# design1.net
KiCad netlist of a schematic drawn in EAGLE
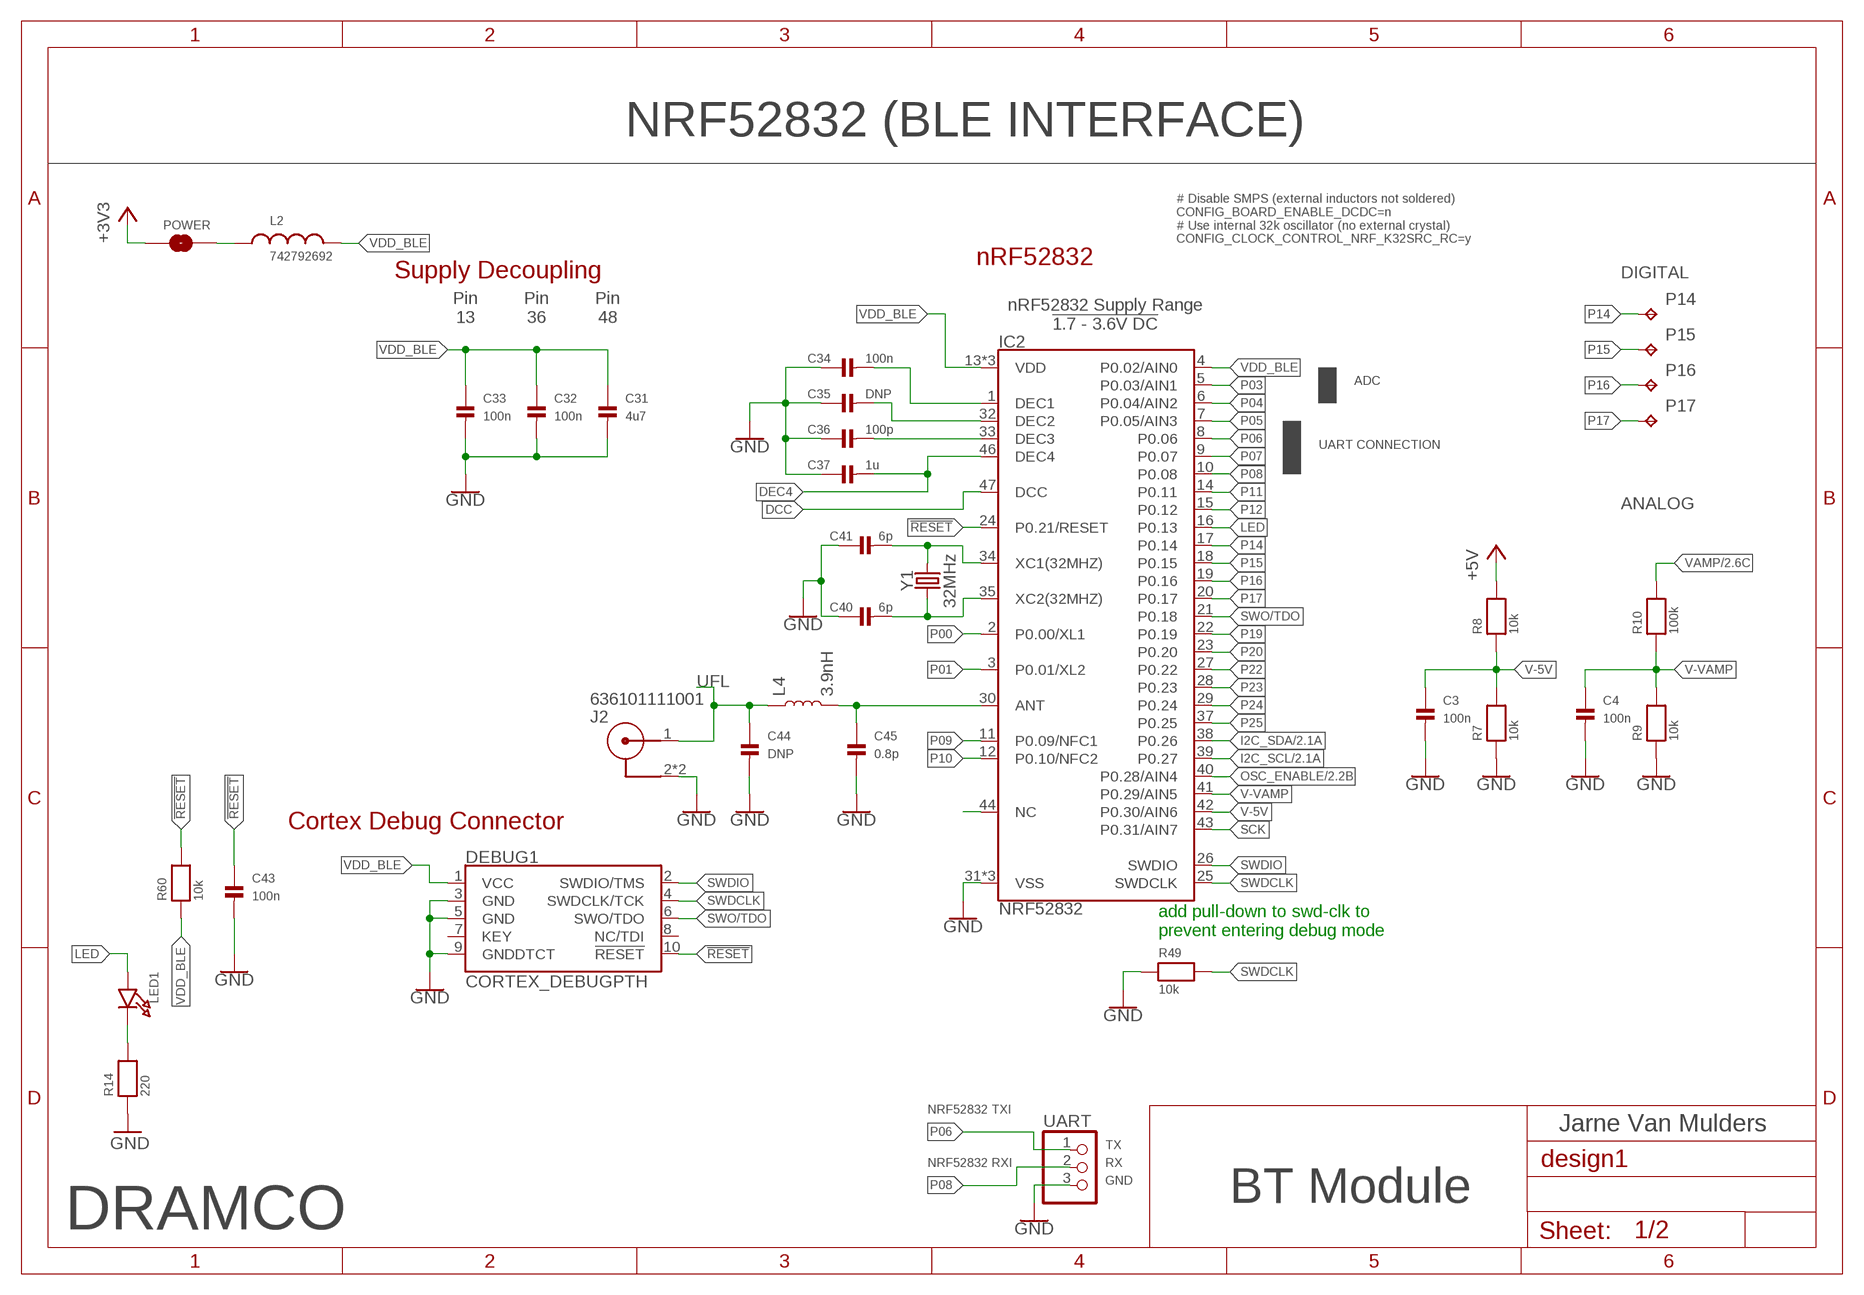
[diagram p0: schematic, sheet 1]
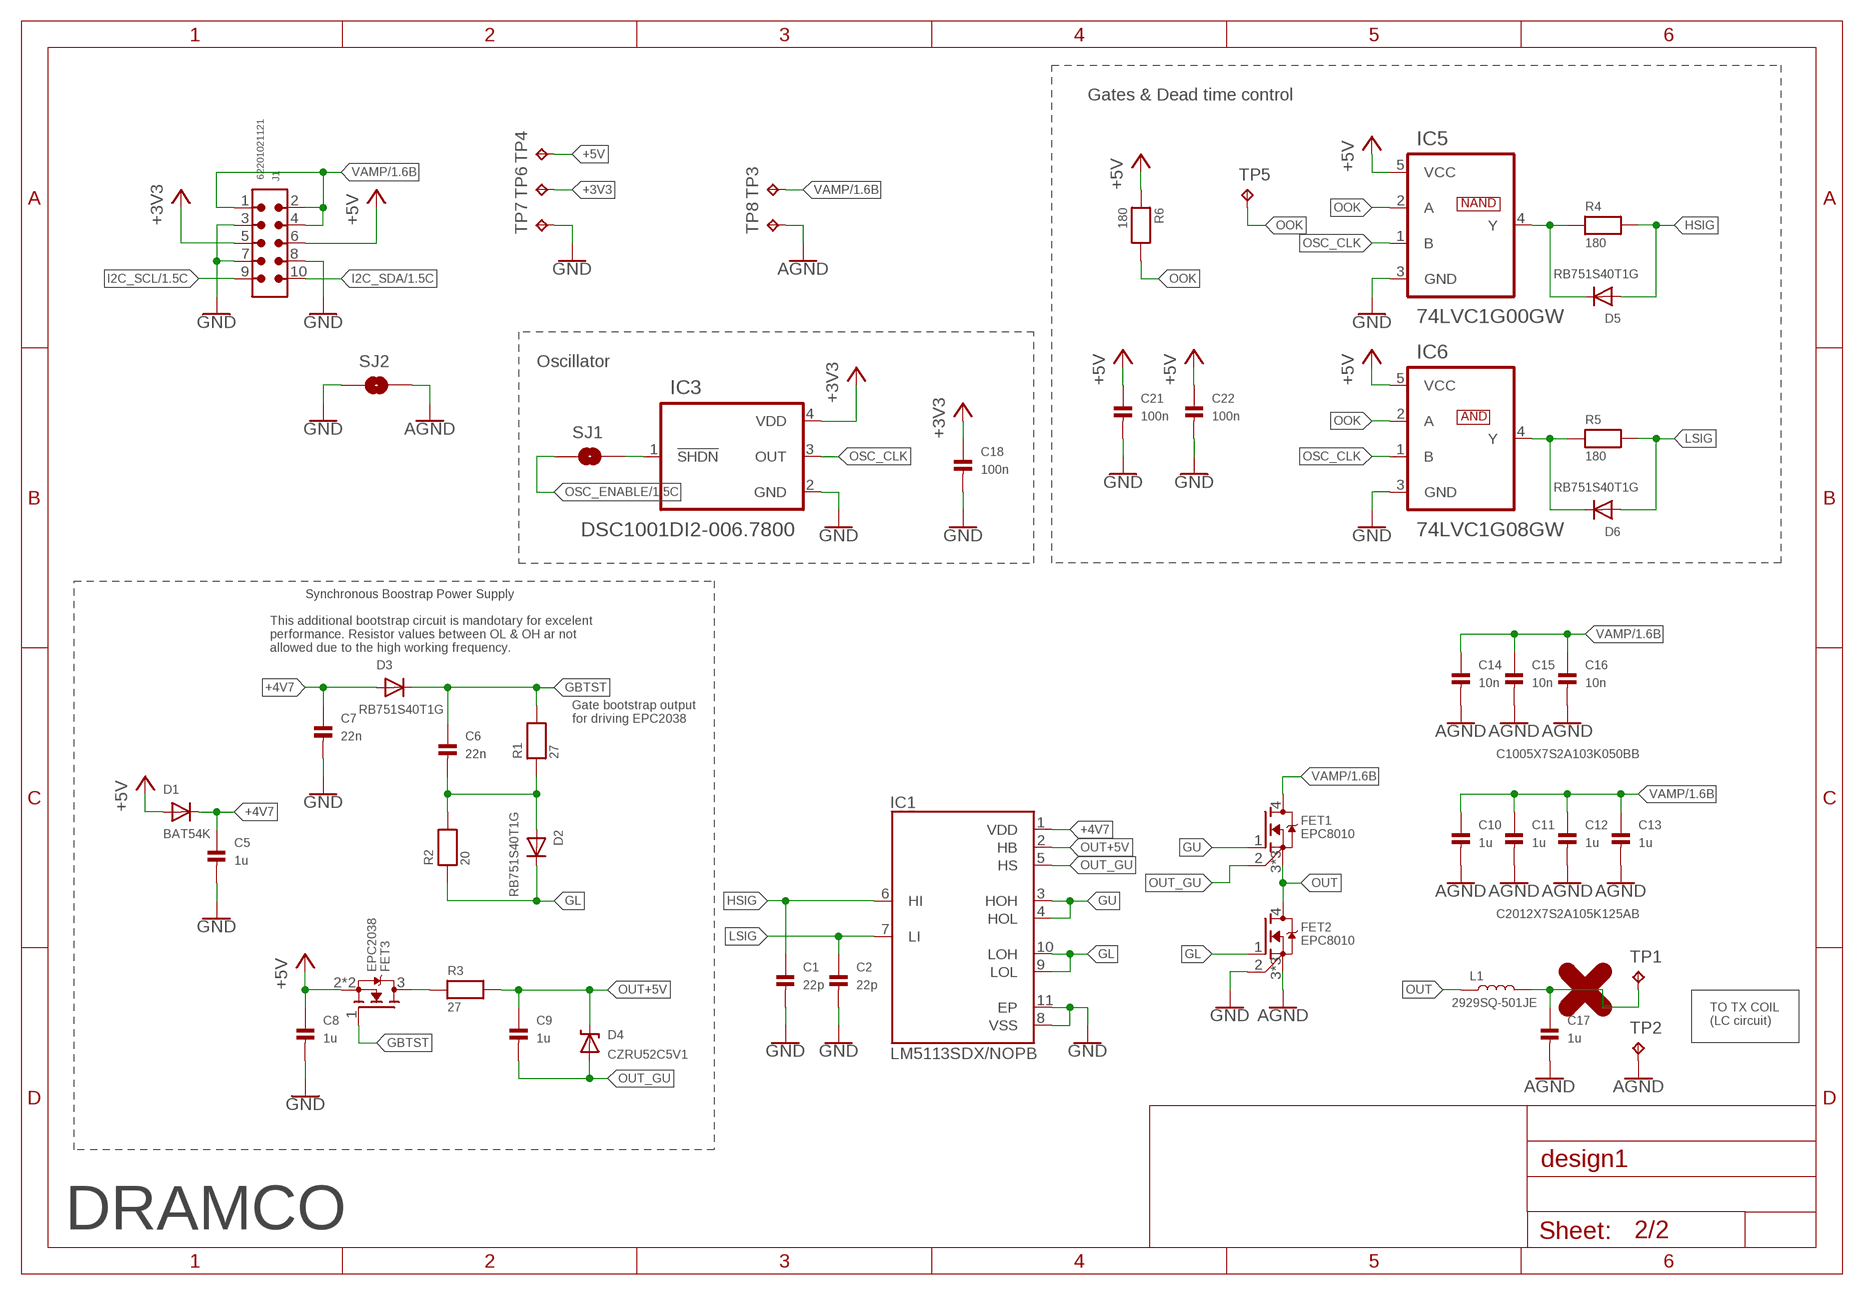
[diagram p1: schematic, sheet 2]

(export (version "E")
  (design (tool "Eeschema 10.0.6"))
  (components
    (comp (ref "C1")
      (value "22p")
      (footprint "eagle-import:0402")
      (libsource (lib "eagle-import") (part "CAP_CERAMIC0402"))
    )
    (comp (ref "C2")
      (value "22p")
      (footprint "eagle-import:0402")
      (libsource (lib "eagle-import") (part "CAP_CERAMIC0402"))
    )
    (comp (ref "C5")
      (value "1u")
      (footprint "eagle-import:0402")
      (libsource (lib "eagle-import") (part "CAP_CERAMIC0402"))
    )
    (comp (ref "C6")
      (value "22n")
      (footprint "eagle-import:0402")
      (libsource (lib "eagle-import") (part "CAP_CERAMIC0402"))
    )
    (comp (ref "C7")
      (value "22n")
      (footprint "eagle-import:0402")
      (libsource (lib "eagle-import") (part "CAP_CERAMIC0402"))
    )
    (comp (ref "C8")
      (value "1u")
      (footprint "eagle-import:0402")
      (libsource (lib "eagle-import") (part "CAP_CERAMIC0402"))
    )
    (comp (ref "C9")
      (value "1u")
      (footprint "eagle-import:0402")
      (libsource (lib "eagle-import") (part "CAP_CERAMIC0402"))
    )
    (comp (ref "C10")
      (value "1u")
      (footprint "eagle-import:0805")
      (libsource (lib "eagle-import") (part "CAP_CERAMIC0805"))
    )
    (comp (ref "C11")
      (value "1u")
      (footprint "eagle-import:0805")
      (libsource (lib "eagle-import") (part "CAP_CERAMIC0805"))
    )
    (comp (ref "C12")
      (value "1u")
      (footprint "eagle-import:0805")
      (libsource (lib "eagle-import") (part "CAP_CERAMIC0805"))
    )
    (comp (ref "C13")
      (value "1u")
      (footprint "eagle-import:0805")
      (libsource (lib "eagle-import") (part "CAP_CERAMIC0805"))
    )
    (comp (ref "C14")
      (value "10n")
      (footprint "eagle-import:0402")
      (libsource (lib "eagle-import") (part "CAP_CERAMIC0402"))
    )
    (comp (ref "C15")
      (value "10n")
      (footprint "eagle-import:0402")
      (libsource (lib "eagle-import") (part "CAP_CERAMIC0402"))
    )
    (comp (ref "C16")
      (value "10n")
      (footprint "eagle-import:0402")
      (libsource (lib "eagle-import") (part "CAP_CERAMIC0402"))
    )
    (comp (ref "C17")
      (value "1u")
      (footprint "eagle-import:0805")
      (libsource (lib "eagle-import") (part "CAP_CERAMIC0805"))
    )
    (comp (ref "C18")
      (value "100n")
      (footprint "eagle-import:0603")
      (libsource (lib "eagle-import") (part "CAP_CERAMIC0603"))
    )
    (comp (ref "C21")
      (value "100n")
      (footprint "eagle-import:0402")
      (libsource (lib "eagle-import") (part "CAP_CERAMIC0402"))
    )
    (comp (ref "C22")
      (value "100n")
      (footprint "eagle-import:0402")
      (libsource (lib "eagle-import") (part "CAP_CERAMIC0402"))
    )
    (comp (ref "D1")
      (value "BAT54K")
      (footprint "eagle-import:SOD-523")
      (libsource (lib "eagle-import") (part "DIODESOD-523"))
    )
    (comp (ref "D2")
      (value "RB751S40T1G")
      (footprint "eagle-import:SOD-523")
      (libsource (lib "eagle-import") (part "DIODESOD-523"))
    )
    (comp (ref "D3")
      (value "RB751S40T1G")
      (footprint "eagle-import:SOD-523")
      (libsource (lib "eagle-import") (part "DIODESOD-523"))
    )
    (comp (ref "D4")
      (value "CZRU52C5V1")
      (footprint "eagle-import:SOD-523F")
      (libsource (lib "eagle-import") (part "CZRU52"))
    )
    (comp (ref "D5")
      (value "RB751S40T1G")
      (footprint "eagle-import:SOD-523")
      (libsource (lib "eagle-import") (part "DIODESOD-523"))
    )
    (comp (ref "D6")
      (value "RB751S40T1G")
      (footprint "eagle-import:SOD-523")
      (libsource (lib "eagle-import") (part "DIODESOD-523"))
    )
    (comp (ref "FET1")
      (value "EPC8010")
      (footprint "eagle-import:BGA-8010")
      (libsource (lib "eagle-import") (part "EPC8010"))
    )
    (comp (ref "FET2")
      (value "EPC8010")
      (footprint "eagle-import:BGA-8010")
      (libsource (lib "eagle-import") (part "EPC8010"))
    )
    (comp (ref "FET3")
      (value "EPC2038")
      (footprint "eagle-import:BGA-2038")
      (libsource (lib "eagle-import") (part "EPC2038"))
    )
    (comp (ref "IC1")
      (value "LM5113SDX/NOPB")
      (footprint "eagle-import:SON80P400X400X80-11N")
      (fields (field (name "MF") "Texas Instruments"))
      (libsource (lib "eagle-import") (part "LM5113SDX/NOPB"))
    )
    (comp (ref "IC3")
      (value "DSC1001DI2-006.7800")
      (footprint "eagle-import:2.5X2.0MMPLASTICPACKAGE")
      (fields (field (name "MF") "Microchip") (field (name "MP") "DSC1001DI1-025.0000"))
      (libsource (lib "eagle-import") (part "DSC1001DI2-006.7800"))
    )
    (comp (ref "IC5")
      (value "74LVC1G00GW")
      (footprint "eagle-import:SOT65P210X110-5N")
      (fields (field (name "MF") "Nexperia USA"))
      (libsource (lib "eagle-import") (part "74LVC1G00GW"))
    )
    (comp (ref "IC6")
      (value "74LVC1G08GW")
      (footprint "eagle-import:SOT65P210X110-5N")
      (fields (field (name "MF") "Nexperia USA") (field (name "MP") "74LVC1G00GW"))
      (libsource (lib "eagle-import") (part "74LVC1G00GW"))
    )
    (comp (ref "J1")
      (value "62201021121")
      (footprint "eagle-import:62201021121")
      (libsource (lib "eagle-import") (part "6220XX21121_62201021121"))
    )
    (comp (ref "L1")
      (value "2929SQ-501JE")
      (footprint "eagle-import:2929SQ-501")
      (libsource (lib "eagle-import") (part "2929SQ-501"))
    )
    (comp (ref "R1")
      (value "27")
      (footprint "eagle-import:0402")
      (libsource (lib "eagle-import") (part "RESISTOR0402"))
    )
    (comp (ref "R2")
      (value "20")
      (footprint "eagle-import:0402")
      (libsource (lib "eagle-import") (part "RESISTOR0402"))
    )
    (comp (ref "R3")
      (value "27")
      (footprint "eagle-import:0402")
      (libsource (lib "eagle-import") (part "RESISTOR0402"))
    )
    (comp (ref "R4")
      (value "180")
      (footprint "eagle-import:0402")
      (libsource (lib "eagle-import") (part "RESISTOR0402"))
    )
    (comp (ref "R5")
      (value "180")
      (footprint "eagle-import:0402")
      (libsource (lib "eagle-import") (part "RESISTOR0402"))
    )
    (comp (ref "R6")
      (value "180")
      (footprint "eagle-import:0402")
      (libsource (lib "eagle-import") (part "RESISTOR0402"))
    )
    (comp (ref "SJ1")
      (value "SOLDERJUMPERNO")
      (footprint "eagle-import:SJ_2S-NO")
      (libsource (lib "eagle-import") (part "SOLDERJUMPERNO"))
    )
    (comp (ref "SJ2")
      (value "SOLDERJUMPERNO")
      (footprint "eagle-import:SJ_2S-NO")
      (libsource (lib "eagle-import") (part "SOLDERJUMPERNO"))
    )
    (comp (ref "TP1")
      (value "TPTP20SQ")
      (footprint "eagle-import:TP20SQ")
      (libsource (lib "eagle-import") (part "TPTP20SQ"))
    )
    (comp (ref "TP2")
      (value "TPTP20SQ")
      (footprint "eagle-import:TP20SQ")
      (libsource (lib "eagle-import") (part "TPTP20SQ"))
    )
    (comp (ref "TP3")
      (value "TPTP20SQ")
      (footprint "eagle-import:TP20SQ")
      (libsource (lib "eagle-import") (part "TPTP20SQ"))
    )
    (comp (ref "TP4")
      (value "TPTP10SQ")
      (footprint "eagle-import:TP10SQ")
      (libsource (lib "eagle-import") (part "TPTP10SQ"))
    )
    (comp (ref "TP5")
      (value "TPTP10SQ")
      (footprint "eagle-import:TP10SQ")
      (libsource (lib "eagle-import") (part "TPTP10SQ"))
    )
    (comp (ref "TP6")
      (value "TPTP10SQ")
      (footprint "eagle-import:TP10SQ")
      (libsource (lib "eagle-import") (part "TPTP10SQ"))
    )
    (comp (ref "TP7")
      (value "TPTP10SQ")
      (footprint "eagle-import:TP10SQ")
      (libsource (lib "eagle-import") (part "TPTP10SQ"))
    )
    (comp (ref "TP8")
      (value "TPTP20SQ")
      (footprint "eagle-import:TP20SQ")
      (libsource (lib "eagle-import") (part "TPTP20SQ"))
    )
    (comp (ref "C3")
      (value "100n")
      (footprint "eagle-import:0402")
      (libsource (lib "eagle-import") (part "CAP_CERAMIC0402"))
    )
    (comp (ref "C4")
      (value "100n")
      (footprint "eagle-import:0402")
      (libsource (lib "eagle-import") (part "CAP_CERAMIC0402"))
    )
    (comp (ref "C31")
      (value "4u7")
      (footprint "eagle-import:0603")
      (libsource (lib "eagle-import") (part "CAP_CERAMIC0603"))
    )
    (comp (ref "C32")
      (value "100n")
      (footprint "eagle-import:0402")
      (libsource (lib "eagle-import") (part "CAP_CERAMIC0402"))
    )
    (comp (ref "C33")
      (value "100n")
      (footprint "eagle-import:0402")
      (libsource (lib "eagle-import") (part "CAP_CERAMIC0402"))
    )
    (comp (ref "C34")
      (value "100n")
      (footprint "eagle-import:0402")
      (libsource (lib "eagle-import") (part "CAP_CERAMIC0402"))
    )
    (comp (ref "C35")
      (value "DNP")
      (footprint "eagle-import:0402")
      (libsource (lib "eagle-import") (part "CAP_CERAMIC0402"))
    )
    (comp (ref "C36")
      (value "100p")
      (footprint "eagle-import:0402")
      (libsource (lib "eagle-import") (part "CAP_CERAMIC0402"))
    )
    (comp (ref "C37")
      (value "1u")
      (footprint "eagle-import:0402")
      (libsource (lib "eagle-import") (part "CAP_CERAMIC0402"))
    )
    (comp (ref "C40")
      (value "6p")
      (footprint "eagle-import:0402")
      (libsource (lib "eagle-import") (part "CAP_CERAMIC0402"))
    )
    (comp (ref "C41")
      (value "6p")
      (footprint "eagle-import:0402")
      (libsource (lib "eagle-import") (part "CAP_CERAMIC0402"))
    )
    (comp (ref "C43")
      (value "100n")
      (footprint "eagle-import:0402")
      (libsource (lib "eagle-import") (part "CAP_CERAMIC0402"))
    )
    (comp (ref "C44")
      (value "DNP")
      (footprint "eagle-import:0402")
      (libsource (lib "eagle-import") (part "CAP_CERAMIC0402"))
    )
    (comp (ref "C45")
      (value "0.8p")
      (footprint "eagle-import:0402")
      (libsource (lib "eagle-import") (part "CAP_CERAMIC0402"))
    )
    (comp (ref "DEBUG1")
      (value "CORTEX_DEBUGPTH")
      (footprint "eagle-import:2X5-PTH-1.27MM")
      (libsource (lib "eagle-import") (part "CORTEX_DEBUGPTH"))
    )
    (comp (ref "IC2")
      (value "NRF52832")
      (footprint "eagle-import:QFN48-6X6MM-EXTENDED")
      (libsource (lib "eagle-import") (part "NRF52832-EXTENDED"))
    )
    (comp (ref "J2")
      (value "636101111001")
      (footprint "eagle-import:636101111001")
      (libsource (lib "eagle-import") (part "636101111001"))
    )
    (comp (ref "L2")
      (value "742792692")
      (footprint "eagle-import:WE-CBF_0603(W=2.2)")
      (libsource (lib "eagle-import") (part "WE-CBF_0603_WB_HS_742792692"))
    )
    (comp (ref "L4")
      (value "3.9nH")
      (footprint "eagle-import:0402")
      (libsource (lib "eagle-import") (part "INDUCTOR-0402-3.9NH"))
    )
    (comp (ref "LED1")
      (value "LED0805")
      (footprint "eagle-import:CHIPLED_0805")
      (libsource (lib "eagle-import") (part "LED0805"))
    )
    (comp (ref "P14")
      (value "TPTP10SQ")
      (footprint "eagle-import:TP10SQ")
      (libsource (lib "eagle-import") (part "TPTP10SQ"))
    )
    (comp (ref "P15")
      (value "TPTP10SQ")
      (footprint "eagle-import:TP10SQ")
      (libsource (lib "eagle-import") (part "TPTP10SQ"))
    )
    (comp (ref "P16")
      (value "TPTP10SQ")
      (footprint "eagle-import:TP10SQ")
      (libsource (lib "eagle-import") (part "TPTP10SQ"))
    )
    (comp (ref "P17")
      (value "TPTP10SQ")
      (footprint "eagle-import:TP10SQ")
      (libsource (lib "eagle-import") (part "TPTP10SQ"))
    )
    (comp (ref "POWER")
      (value "JUMPER-SMT_2_NO_NO-SILK")
      (footprint "eagle-import:SMT-JUMPER_2_NO_NO-SILK")
      (libsource (lib "eagle-import") (part "JUMPER-SMT_2_NO_NO-SILK"))
    )
    (comp (ref "R7")
      (value "10k")
      (footprint "eagle-import:0402")
      (libsource (lib "eagle-import") (part "RESISTOR0402"))
    )
    (comp (ref "R8")
      (value "10k")
      (footprint "eagle-import:0402")
      (libsource (lib "eagle-import") (part "RESISTOR0402"))
    )
    (comp (ref "R9")
      (value "10k")
      (footprint "eagle-import:0402")
      (libsource (lib "eagle-import") (part "RESISTOR0402"))
    )
    (comp (ref "R10")
      (value "100k")
      (footprint "eagle-import:0402")
      (libsource (lib "eagle-import") (part "RESISTOR0402"))
    )
    (comp (ref "R14")
      (value "220")
      (footprint "eagle-import:0603")
      (libsource (lib "eagle-import") (part "RESISTOR0603"))
    )
    (comp (ref "R49")
      (value "10k")
      (footprint "eagle-import:0402")
      (libsource (lib "eagle-import") (part "RESISTOR0402"))
    )
    (comp (ref "R60")
      (value "10k")
      (footprint "eagle-import:0402")
      (libsource (lib "eagle-import") (part "RESISTOR0402"))
    )
    (comp (ref "UART")
      (value "HEADER-1X3ROUND")
      (footprint "eagle-import:1X03_ROUND")
      (libsource (lib "eagle-import") (part "HEADER-1X3ROUND"))
    )
    (comp (ref "Y1")
      (value "32MHz")
      (footprint "eagle-import:CRYSTAL-SMD-2.0X1.6MM")
      (libsource (lib "eagle-import") (part "CRYSTAL-32MHZ-SMD-2.0X1.6MM"))
    )
  )
  (nets
    (net (code "1") (name "+3V3") (class "Default")
      (node (ref "C18") (pin "1") (pinfunction "P$1_1") (pintype "passive"))
      (node (ref "IC3") (pin "4") (pinfunction "VDD_4") (pintype "power_in"))
      (node (ref "J1") (pin "5") (pinfunction "5_5") (pintype "passive"))
      (node (ref "POWER") (pin "1") (pinfunction "1_1") (pintype "passive"))
      (node (ref "TP6") (pin "TP") (pinfunction "TP_TP") (pintype "input"))
    )
    (net (code "2") (name "+4V7") (class "Default")
      (node (ref "C5") (pin "1") (pinfunction "P$1_1") (pintype "passive"))
      (node (ref "C7") (pin "1") (pinfunction "P$1_1") (pintype "passive"))
      (node (ref "D1") (pin "K") (pinfunction "C_K") (pintype "passive"))
      (node (ref "D3") (pin "A") (pinfunction "A_A") (pintype "passive"))
      (node (ref "IC1") (pin "1") (pinfunction "VDD_1") (pintype "power_in"))
    )
    (net (code "3") (name "+5V") (class "Default")
      (node (ref "C21") (pin "1") (pinfunction "P$1_1") (pintype "passive"))
      (node (ref "C22") (pin "1") (pinfunction "P$1_1") (pintype "passive"))
      (node (ref "C8") (pin "1") (pinfunction "P$1_1") (pintype "passive"))
      (node (ref "D1") (pin "A") (pinfunction "A_A") (pintype "passive"))
      (node (ref "FET3") (pin "2") (pinfunction "S_2") (pintype "bidirectional"))
      (node (ref "FET3") (pin "4") (pinfunction "S_4") (pintype "bidirectional"))
      (node (ref "IC5") (pin "5") (pinfunction "VCC_5") (pintype "power_in"))
      (node (ref "IC6") (pin "5") (pinfunction "VCC_5") (pintype "power_in"))
      (node (ref "J1") (pin "6") (pinfunction "6_6") (pintype "passive"))
      (node (ref "R6") (pin "1") (pinfunction "1_1") (pintype "passive"))
      (node (ref "R8") (pin "2") (pinfunction "2_2") (pintype "passive"))
      (node (ref "TP4") (pin "TP") (pinfunction "TP_TP") (pintype "input"))
    )
    (net (code "4") (name "AGND") (class "Default")
      (node (ref "C10") (pin "2") (pinfunction "P$2_2") (pintype "passive"))
      (node (ref "C11") (pin "2") (pinfunction "P$2_2") (pintype "passive"))
      (node (ref "C12") (pin "2") (pinfunction "P$2_2") (pintype "passive"))
      (node (ref "C13") (pin "2") (pinfunction "P$2_2") (pintype "passive"))
      (node (ref "C14") (pin "2") (pinfunction "P$2_2") (pintype "passive"))
      (node (ref "C15") (pin "2") (pinfunction "P$2_2") (pintype "passive"))
      (node (ref "C16") (pin "2") (pinfunction "P$2_2") (pintype "passive"))
      (node (ref "C17") (pin "2") (pinfunction "P$2_2") (pintype "passive"))
      (node (ref "FET2") (pin "3") (pinfunction "S_3") (pintype "bidirectional"))
      (node (ref "FET2") (pin "5") (pinfunction "S_5") (pintype "bidirectional"))
      (node (ref "FET2") (pin "6") (pinfunction "S_6") (pintype "bidirectional"))
      (node (ref "SJ2") (pin "2") (pinfunction "2_2") (pintype "passive"))
      (node (ref "TP2") (pin "TP") (pinfunction "TP_TP") (pintype "input"))
      (node (ref "TP8") (pin "TP") (pinfunction "TP_TP") (pintype "input"))
    )
    (net (code "5") (name "DCC") (class "Default")
      (node (ref "IC2") (pin "47") (pinfunction "DCC_47") (pintype "bidirectional"))
    )
    (net (code "6") (name "DEC4") (class "Default")
      (node (ref "C37") (pin "2") (pinfunction "P$2_2") (pintype "passive"))
      (node (ref "IC2") (pin "46") (pinfunction "DEC4_46") (pintype "bidirectional"))
    )
    (net (code "7") (name "GBTST") (class "Default")
      (node (ref "C6") (pin "1") (pinfunction "P$1_1") (pintype "passive"))
      (node (ref "D3") (pin "K") (pinfunction "C_K") (pintype "passive"))
      (node (ref "FET3") (pin "1") (pinfunction "G_1") (pintype "bidirectional"))
      (node (ref "R1") (pin "2") (pinfunction "2_2") (pintype "passive"))
    )
    (net (code "8") (name "GL") (class "Default")
      (node (ref "D2") (pin "K") (pinfunction "C_K") (pintype "passive"))
      (node (ref "FET2") (pin "1") (pinfunction "G_1") (pintype "bidirectional"))
      (node (ref "IC1") (pin "10") (pinfunction "LOH_10") (pintype "output"))
      (node (ref "IC1") (pin "9") (pinfunction "LOL_9") (pintype "output"))
      (node (ref "R2") (pin "1") (pinfunction "1_1") (pintype "passive"))
    )
    (net (code "9") (name "GND") (class "Default")
      (node (ref "C1") (pin "2") (pinfunction "P$2_2") (pintype "passive"))
      (node (ref "C18") (pin "2") (pinfunction "P$2_2") (pintype "passive"))
      (node (ref "C2") (pin "2") (pinfunction "P$2_2") (pintype "passive"))
      (node (ref "C21") (pin "2") (pinfunction "P$2_2") (pintype "passive"))
      (node (ref "C22") (pin "2") (pinfunction "P$2_2") (pintype "passive"))
      (node (ref "C3") (pin "2") (pinfunction "P$2_2") (pintype "passive"))
      (node (ref "C31") (pin "2") (pinfunction "P$2_2") (pintype "passive"))
      (node (ref "C32") (pin "2") (pinfunction "P$2_2") (pintype "passive"))
      (node (ref "C33") (pin "2") (pinfunction "P$2_2") (pintype "passive"))
      (node (ref "C34") (pin "1") (pinfunction "P$1_1") (pintype "passive"))
      (node (ref "C35") (pin "1") (pinfunction "P$1_1") (pintype "passive"))
      (node (ref "C36") (pin "1") (pinfunction "P$1_1") (pintype "passive"))
      (node (ref "C37") (pin "1") (pinfunction "P$1_1") (pintype "passive"))
      (node (ref "C4") (pin "2") (pinfunction "P$2_2") (pintype "passive"))
      (node (ref "C40") (pin "1") (pinfunction "P$1_1") (pintype "passive"))
      (node (ref "C41") (pin "1") (pinfunction "P$1_1") (pintype "passive"))
      (node (ref "C43") (pin "2") (pinfunction "P$2_2") (pintype "passive"))
      (node (ref "C44") (pin "2") (pinfunction "P$2_2") (pintype "passive"))
      (node (ref "C45") (pin "2") (pinfunction "P$2_2") (pintype "passive"))
      (node (ref "C5") (pin "2") (pinfunction "P$2_2") (pintype "passive"))
      (node (ref "C7") (pin "2") (pinfunction "P$2_2") (pintype "passive"))
      (node (ref "C8") (pin "2") (pinfunction "P$2_2") (pintype "passive"))
      (node (ref "DEBUG1") (pin "3") (pinfunction "GND_3") (pintype "bidirectional"))
      (node (ref "DEBUG1") (pin "5") (pinfunction "GND_5") (pintype "bidirectional"))
      (node (ref "DEBUG1") (pin "9") (pinfunction "GNDDTCT_9") (pintype "bidirectional"))
      (node (ref "FET2") (pin "2") (pinfunction "SR_2") (pintype "bidirectional"))
      (node (ref "IC1") (pin "11") (pinfunction "EP_11") (pintype "power_in"))
      (node (ref "IC1") (pin "8") (pinfunction "VSS_8") (pintype "power_in"))
      (node (ref "IC2") (pin "31") (pinfunction "VSS_31") (pintype "bidirectional"))
      (node (ref "IC2") (pin "45") (pinfunction "VSS_45") (pintype "bidirectional"))
      (node (ref "IC2") (pin "EP") (pinfunction "VSS_EP") (pintype "bidirectional"))
      (node (ref "IC3") (pin "2") (pinfunction "GND_2") (pintype "power_in"))
      (node (ref "IC5") (pin "3") (pinfunction "GND_3") (pintype "passive"))
      (node (ref "IC6") (pin "3") (pinfunction "GND_3") (pintype "passive"))
      (node (ref "J1") (pin "3") (pinfunction "3_3") (pintype "passive"))
      (node (ref "J1") (pin "7") (pinfunction "7_7") (pintype "passive"))
      (node (ref "J1") (pin "8") (pinfunction "8_8") (pintype "passive"))
      (node (ref "J2") (pin "2") (pinfunction "2_2") (pintype "passive"))
      (node (ref "J2") (pin "3") (pinfunction "2_3") (pintype "passive"))
      (node (ref "R14") (pin "1") (pinfunction "1_1") (pintype "passive"))
      (node (ref "R49") (pin "1") (pinfunction "1_1") (pintype "passive"))
      (node (ref "R7") (pin "1") (pinfunction "1_1") (pintype "passive"))
      (node (ref "R9") (pin "1") (pinfunction "1_1") (pintype "passive"))
      (node (ref "SJ2") (pin "1") (pinfunction "1_1") (pintype "passive"))
      (node (ref "TP7") (pin "TP") (pinfunction "TP_TP") (pintype "input"))
      (node (ref "UART") (pin "3") (pinfunction "3_3") (pintype "passive"))
    )
    (net (code "10") (name "GU") (class "Default")
      (node (ref "FET1") (pin "1") (pinfunction "G_1") (pintype "bidirectional"))
      (node (ref "IC1") (pin "3") (pinfunction "HOH_3") (pintype "output"))
      (node (ref "IC1") (pin "4") (pinfunction "HOL_4") (pintype "output"))
    )
    (net (code "11") (name "HSIG") (class "Default")
      (node (ref "C1") (pin "1") (pinfunction "P$1_1") (pintype "passive"))
      (node (ref "D5") (pin "A") (pinfunction "A_A") (pintype "passive"))
      (node (ref "IC1") (pin "6") (pinfunction "HI_6") (pintype "input"))
      (node (ref "R4") (pin "2") (pinfunction "2_2") (pintype "passive"))
    )
    (net (code "12") (name "I2C_SCL") (class "Default")
      (node (ref "IC2") (pin "39") (pinfunction "P0.27_39") (pintype "bidirectional"))
      (node (ref "J1") (pin "9") (pinfunction "9_9") (pintype "passive"))
    )
    (net (code "13") (name "I2C_SDA") (class "Default")
      (node (ref "IC2") (pin "38") (pinfunction "P0.26_38") (pintype "bidirectional"))
      (node (ref "J1") (pin "10") (pinfunction "10_10") (pintype "passive"))
    )
    (net (code "14") (name "LED") (class "Default")
      (node (ref "IC2") (pin "16") (pinfunction "P0.13_16") (pintype "bidirectional"))
      (node (ref "LED1") (pin "A") (pinfunction "A_A") (pintype "passive"))
    )
    (net (code "15") (name "LSIG") (class "Default")
      (node (ref "C2") (pin "1") (pinfunction "P$1_1") (pintype "passive"))
      (node (ref "D6") (pin "A") (pinfunction "A_A") (pintype "passive"))
      (node (ref "IC1") (pin "7") (pinfunction "LI_7") (pintype "input"))
      (node (ref "R5") (pin "2") (pinfunction "2_2") (pintype "passive"))
    )
    (net (code "16") (name "Net-(C6-P$2)") (class "Default")
      (node (ref "C6") (pin "2") (pinfunction "P$2_2") (pintype "passive"))
      (node (ref "D2") (pin "A") (pinfunction "A_A") (pintype "passive"))
      (node (ref "R1") (pin "1") (pinfunction "1_1") (pintype "passive"))
      (node (ref "R2") (pin "2") (pinfunction "2_2") (pintype "passive"))
    )
    (net (code "17") (name "Net-(C17-P$1)") (class "Default")
      (node (ref "C17") (pin "1") (pinfunction "P$1_1") (pintype "passive"))
      (node (ref "L1") (pin "2") (pinfunction "2_2") (pintype "bidirectional"))
      (node (ref "TP1") (pin "TP") (pinfunction "TP_TP") (pintype "input"))
    )
    (net (code "18") (name "Net-(C34-P$2)") (class "Default")
      (node (ref "C34") (pin "2") (pinfunction "P$2_2") (pintype "passive"))
      (node (ref "IC2") (pin "1") (pinfunction "DEC1_1") (pintype "bidirectional"))
    )
    (net (code "19") (name "Net-(C35-P$2)") (class "Default")
      (node (ref "C35") (pin "2") (pinfunction "P$2_2") (pintype "passive"))
      (node (ref "IC2") (pin "32") (pinfunction "DEC2_32") (pintype "bidirectional"))
    )
    (net (code "20") (name "Net-(C36-P$2)") (class "Default")
      (node (ref "C36") (pin "2") (pinfunction "P$2_2") (pintype "passive"))
      (node (ref "IC2") (pin "33") (pinfunction "DEC3_33") (pintype "bidirectional"))
    )
    (net (code "21") (name "Net-(C40-P$2)") (class "Default")
      (node (ref "C40") (pin "2") (pinfunction "P$2_2") (pintype "passive"))
      (node (ref "IC2") (pin "35") (pinfunction "XC2(32MHZ)_35") (pintype "bidirectional"))
      (node (ref "Y1") (pin "1") (pinfunction "1_1") (pintype "passive"))
    )
    (net (code "22") (name "Net-(C41-P$2)") (class "Default")
      (node (ref "C41") (pin "2") (pinfunction "P$2_2") (pintype "passive"))
      (node (ref "IC2") (pin "34") (pinfunction "XC1(32MHZ)_34") (pintype "bidirectional"))
      (node (ref "Y1") (pin "3") (pinfunction "2_3") (pintype "passive"))
    )
    (net (code "23") (name "Net-(C45-P$1)") (class "Default")
      (node (ref "C45") (pin "1") (pinfunction "P$1_1") (pintype "passive"))
      (node (ref "IC2") (pin "30") (pinfunction "ANT_30") (pintype "bidirectional"))
      (node (ref "L4") (pin "2") (pinfunction "2_2") (pintype "passive"))
    )
    (net (code "24") (name "Net-(D5-C)") (class "Default")
      (node (ref "D5") (pin "K") (pinfunction "C_K") (pintype "passive"))
      (node (ref "IC5") (pin "4") (pinfunction "Y_4") (pintype "output"))
      (node (ref "R4") (pin "1") (pinfunction "1_1") (pintype "passive"))
    )
    (net (code "25") (name "Net-(D6-C)") (class "Default")
      (node (ref "D6") (pin "K") (pinfunction "C_K") (pintype "passive"))
      (node (ref "IC6") (pin "4") (pinfunction "Y_4") (pintype "output"))
      (node (ref "R5") (pin "1") (pinfunction "1_1") (pintype "passive"))
    )
    (net (code "26") (name "Net-(FET3-D)") (class "Default")
      (node (ref "FET3") (pin "3") (pinfunction "D_3") (pintype "bidirectional"))
      (node (ref "R3") (pin "1") (pinfunction "1_1") (pintype "passive"))
    )
    (net (code "27") (name "Net-(IC3-~{SHDN})") (class "Default")
      (node (ref "IC3") (pin "1") (pinfunction "~{SHDN}_1") (pintype "input"))
      (node (ref "SJ1") (pin "2") (pinfunction "2_2") (pintype "passive"))
    )
    (net (code "28") (name "Net-(L2-Pad1)") (class "Default")
      (node (ref "L2") (pin "1") (pinfunction "1_1") (pintype "passive"))
      (node (ref "POWER") (pin "2") (pinfunction "2_2") (pintype "passive"))
    )
    (net (code "29") (name "Net-(LED1-PadC)") (class "Default")
      (node (ref "LED1") (pin "C") (pinfunction "C_C") (pintype "passive"))
      (node (ref "R14") (pin "2") (pinfunction "2_2") (pintype "passive"))
    )
    (net (code "30") (name "OOK") (class "Default")
      (node (ref "IC5") (pin "2") (pinfunction "A_2") (pintype "input"))
      (node (ref "IC6") (pin "2") (pinfunction "A_2") (pintype "input"))
      (node (ref "R6") (pin "2") (pinfunction "2_2") (pintype "passive"))
      (node (ref "TP5") (pin "TP") (pinfunction "TP_TP") (pintype "input"))
    )
    (net (code "31") (name "OSC_CLK") (class "Default")
      (node (ref "IC3") (pin "3") (pinfunction "OUT_3") (pintype "output"))
      (node (ref "IC5") (pin "1") (pinfunction "B_1") (pintype "input"))
      (node (ref "IC6") (pin "1") (pinfunction "B_1") (pintype "input"))
    )
    (net (code "32") (name "OSC_ENABLE") (class "Default")
      (node (ref "IC2") (pin "40") (pinfunction "P0.28/AIN4_40") (pintype "bidirectional"))
      (node (ref "SJ1") (pin "1") (pinfunction "1_1") (pintype "passive"))
    )
    (net (code "33") (name "OUT") (class "Default")
      (node (ref "FET1") (pin "3") (pinfunction "S_3") (pintype "bidirectional"))
      (node (ref "FET1") (pin "5") (pinfunction "S_5") (pintype "bidirectional"))
      (node (ref "FET1") (pin "6") (pinfunction "S_6") (pintype "bidirectional"))
      (node (ref "FET2") (pin "4") (pinfunction "D_4") (pintype "bidirectional"))
      (node (ref "L1") (pin "1") (pinfunction "1_1") (pintype "bidirectional"))
    )
    (net (code "34") (name "OUT+5V") (class "Default")
      (node (ref "C9") (pin "1") (pinfunction "P$1_1") (pintype "passive"))
      (node (ref "D4") (pin "1") (pinfunction "C_1") (pintype "passive"))
      (node (ref "IC1") (pin "2") (pinfunction "HB_2") (pintype "power_in"))
      (node (ref "R3") (pin "2") (pinfunction "2_2") (pintype "passive"))
    )
    (net (code "35") (name "OUT_GU") (class "Default")
      (node (ref "C9") (pin "2") (pinfunction "P$2_2") (pintype "passive"))
      (node (ref "D4") (pin "2") (pinfunction "A_2") (pintype "passive"))
      (node (ref "FET1") (pin "2") (pinfunction "SR_2") (pintype "bidirectional"))
      (node (ref "IC1") (pin "5") (pinfunction "HS_5") (pintype "power_in"))
    )
    (net (code "36") (name "P00") (class "Default")
      (node (ref "IC2") (pin "2") (pinfunction "P0.00/XL1_2") (pintype "bidirectional"))
    )
    (net (code "37") (name "P01") (class "Default")
      (node (ref "IC2") (pin "3") (pinfunction "P0.01/XL2_3") (pintype "bidirectional"))
    )
    (net (code "38") (name "P03") (class "Default")
      (node (ref "IC2") (pin "5") (pinfunction "P0.03/AIN1_5") (pintype "bidirectional"))
    )
    (net (code "39") (name "P04") (class "Default")
      (node (ref "IC2") (pin "6") (pinfunction "P0.04/AIN2_6") (pintype "bidirectional"))
    )
    (net (code "40") (name "P05") (class "Default")
      (node (ref "IC2") (pin "7") (pinfunction "P0.05/AIN3_7") (pintype "bidirectional"))
    )
    (net (code "41") (name "P06") (class "Default")
      (node (ref "IC2") (pin "8") (pinfunction "P0.06_8") (pintype "bidirectional"))
      (node (ref "UART") (pin "1") (pinfunction "1_1") (pintype "passive"))
    )
    (net (code "42") (name "P07") (class "Default")
      (node (ref "IC2") (pin "9") (pinfunction "P0.07_9") (pintype "bidirectional"))
    )
    (net (code "43") (name "P08") (class "Default")
      (node (ref "IC2") (pin "10") (pinfunction "P0.08_10") (pintype "bidirectional"))
      (node (ref "UART") (pin "2") (pinfunction "2_2") (pintype "passive"))
    )
    (net (code "44") (name "P09") (class "Default")
      (node (ref "IC2") (pin "11") (pinfunction "P0.09/NFC1_11") (pintype "bidirectional"))
    )
    (net (code "45") (name "P10") (class "Default")
      (node (ref "IC2") (pin "12") (pinfunction "P0.10/NFC2_12") (pintype "bidirectional"))
    )
    (net (code "46") (name "P11") (class "Default")
      (node (ref "IC2") (pin "14") (pinfunction "P0.11_14") (pintype "bidirectional"))
    )
    (net (code "47") (name "P12") (class "Default")
      (node (ref "IC2") (pin "15") (pinfunction "P0.12_15") (pintype "bidirectional"))
    )
    (net (code "48") (name "P14") (class "Default")
      (node (ref "IC2") (pin "17") (pinfunction "P0.14_17") (pintype "bidirectional"))
      (node (ref "P14") (pin "TP") (pinfunction "TP_TP") (pintype "input"))
    )
    (net (code "49") (name "P15") (class "Default")
      (node (ref "IC2") (pin "18") (pinfunction "P0.15_18") (pintype "bidirectional"))
      (node (ref "P15") (pin "TP") (pinfunction "TP_TP") (pintype "input"))
    )
    (net (code "50") (name "P16") (class "Default")
      (node (ref "IC2") (pin "19") (pinfunction "P0.16_19") (pintype "bidirectional"))
      (node (ref "P16") (pin "TP") (pinfunction "TP_TP") (pintype "input"))
    )
    (net (code "51") (name "P17") (class "Default")
      (node (ref "IC2") (pin "20") (pinfunction "P0.17_20") (pintype "bidirectional"))
      (node (ref "P17") (pin "TP") (pinfunction "TP_TP") (pintype "input"))
    )
    (net (code "52") (name "P19") (class "Default")
      (node (ref "IC2") (pin "22") (pinfunction "P0.19_22") (pintype "bidirectional"))
    )
    (net (code "53") (name "P20") (class "Default")
      (node (ref "IC2") (pin "23") (pinfunction "P0.20_23") (pintype "bidirectional"))
    )
    (net (code "54") (name "P22") (class "Default")
      (node (ref "IC2") (pin "27") (pinfunction "P0.22_27") (pintype "bidirectional"))
    )
    (net (code "55") (name "P23") (class "Default")
      (node (ref "IC2") (pin "28") (pinfunction "P0.23_28") (pintype "bidirectional"))
    )
    (net (code "56") (name "P24") (class "Default")
      (node (ref "IC2") (pin "29") (pinfunction "P0.24_29") (pintype "bidirectional"))
    )
    (net (code "57") (name "P25") (class "Default")
      (node (ref "IC2") (pin "37") (pinfunction "P0.25_37") (pintype "bidirectional"))
    )
    (net (code "58") (name "SCK") (class "Default")
      (node (ref "IC2") (pin "43") (pinfunction "P0.31/AIN7_43") (pintype "bidirectional"))
    )
    (net (code "59") (name "SWDCLK") (class "Default")
      (node (ref "DEBUG1") (pin "4") (pinfunction "SWDCLK/TCK_4") (pintype "bidirectional"))
      (node (ref "IC2") (pin "25") (pinfunction "SWDCLK_25") (pintype "bidirectional"))
      (node (ref "R49") (pin "2") (pinfunction "2_2") (pintype "passive"))
    )
    (net (code "60") (name "SWDIO") (class "Default")
      (node (ref "DEBUG1") (pin "2") (pinfunction "SWDIO/TMS_2") (pintype "bidirectional"))
      (node (ref "IC2") (pin "26") (pinfunction "SWDIO_26") (pintype "bidirectional"))
    )
    (net (code "61") (name "SWO{slash}TDO") (class "Default")
      (node (ref "DEBUG1") (pin "6") (pinfunction "SWO/TDO_6") (pintype "bidirectional"))
      (node (ref "IC2") (pin "21") (pinfunction "P0.18_21") (pintype "bidirectional"))
    )
    (net (code "62") (name "UFL") (class "Default")
      (node (ref "C44") (pin "1") (pinfunction "P$1_1") (pintype "passive"))
      (node (ref "J2") (pin "1") (pinfunction "1_1") (pintype "passive"))
      (node (ref "L4") (pin "1") (pinfunction "1_1") (pintype "passive"))
    )
    (net (code "63") (name "V-5V") (class "Default")
      (node (ref "C3") (pin "1") (pinfunction "P$1_1") (pintype "passive"))
      (node (ref "IC2") (pin "42") (pinfunction "P0.30/AIN6_42") (pintype "bidirectional"))
      (node (ref "R7") (pin "2") (pinfunction "2_2") (pintype "passive"))
      (node (ref "R8") (pin "1") (pinfunction "1_1") (pintype "passive"))
    )
    (net (code "64") (name "V-VAMP") (class "Default")
      (node (ref "C4") (pin "1") (pinfunction "P$1_1") (pintype "passive"))
      (node (ref "IC2") (pin "41") (pinfunction "P0.29/AIN5_41") (pintype "bidirectional"))
      (node (ref "R10") (pin "1") (pinfunction "1_1") (pintype "passive"))
      (node (ref "R9") (pin "2") (pinfunction "2_2") (pintype "passive"))
    )
    (net (code "65") (name "VAMP") (class "Default")
      (node (ref "C10") (pin "1") (pinfunction "P$1_1") (pintype "passive"))
      (node (ref "C11") (pin "1") (pinfunction "P$1_1") (pintype "passive"))
      (node (ref "C12") (pin "1") (pinfunction "P$1_1") (pintype "passive"))
      (node (ref "C13") (pin "1") (pinfunction "P$1_1") (pintype "passive"))
      (node (ref "C14") (pin "1") (pinfunction "P$1_1") (pintype "passive"))
      (node (ref "C15") (pin "1") (pinfunction "P$1_1") (pintype "passive"))
      (node (ref "C16") (pin "1") (pinfunction "P$1_1") (pintype "passive"))
      (node (ref "FET1") (pin "4") (pinfunction "D_4") (pintype "bidirectional"))
      (node (ref "J1") (pin "1") (pinfunction "1_1") (pintype "passive"))
      (node (ref "J1") (pin "2") (pinfunction "2_2") (pintype "passive"))
      (node (ref "J1") (pin "4") (pinfunction "4_4") (pintype "passive"))
      (node (ref "R10") (pin "2") (pinfunction "2_2") (pintype "passive"))
      (node (ref "TP3") (pin "TP") (pinfunction "TP_TP") (pintype "input"))
    )
    (net (code "66") (name "VDD_BLE") (class "Default")
      (node (ref "C31") (pin "1") (pinfunction "P$1_1") (pintype "passive"))
      (node (ref "C32") (pin "1") (pinfunction "P$1_1") (pintype "passive"))
      (node (ref "C33") (pin "1") (pinfunction "P$1_1") (pintype "passive"))
      (node (ref "DEBUG1") (pin "1") (pinfunction "VCC_1") (pintype "bidirectional"))
      (node (ref "IC2") (pin "13") (pinfunction "VDD_13") (pintype "bidirectional"))
      (node (ref "IC2") (pin "36") (pinfunction "VDD_36") (pintype "bidirectional"))
      (node (ref "IC2") (pin "4") (pinfunction "P0.02/AIN0_4") (pintype "bidirectional"))
      (node (ref "IC2") (pin "48") (pinfunction "VDD_48") (pintype "bidirectional"))
      (node (ref "L2") (pin "2") (pinfunction "2_2") (pintype "passive"))
      (node (ref "R60") (pin "1") (pinfunction "1_1") (pintype "passive"))
    )
    (net (code "67") (name "unconnected-(DEBUG1-KEY-Pad7)") (class "Default")
      (node (ref "DEBUG1") (pin "7") (pinfunction "KEY_7") (pintype "bidirectional"))
    )
    (net (code "68") (name "unconnected-(DEBUG1-NC{slash}TDI-Pad8)") (class "Default")
      (node (ref "DEBUG1") (pin "8") (pinfunction "NC/TDI_8") (pintype "bidirectional"))
    )
    (net (code "69") (name "unconnected-(IC2-NC-Pad44)") (class "Default")
      (node (ref "IC2") (pin "44") (pinfunction "NC_44") (pintype "bidirectional"))
    )
    (net (code "70") (name "~{RESET}") (class "Default")
      (node (ref "C43") (pin "1") (pinfunction "P$1_1") (pintype "passive"))
      (node (ref "DEBUG1") (pin "10") (pinfunction "~{RESET}_10") (pintype "bidirectional"))
      (node (ref "IC2") (pin "24") (pinfunction "P0.21/RESET_24") (pintype "bidirectional"))
      (node (ref "R60") (pin "2") (pinfunction "2_2") (pintype "passive"))
    )
  )
)
